# CAN.net
KiCad netlist of a schematic drawn in Altium Designer
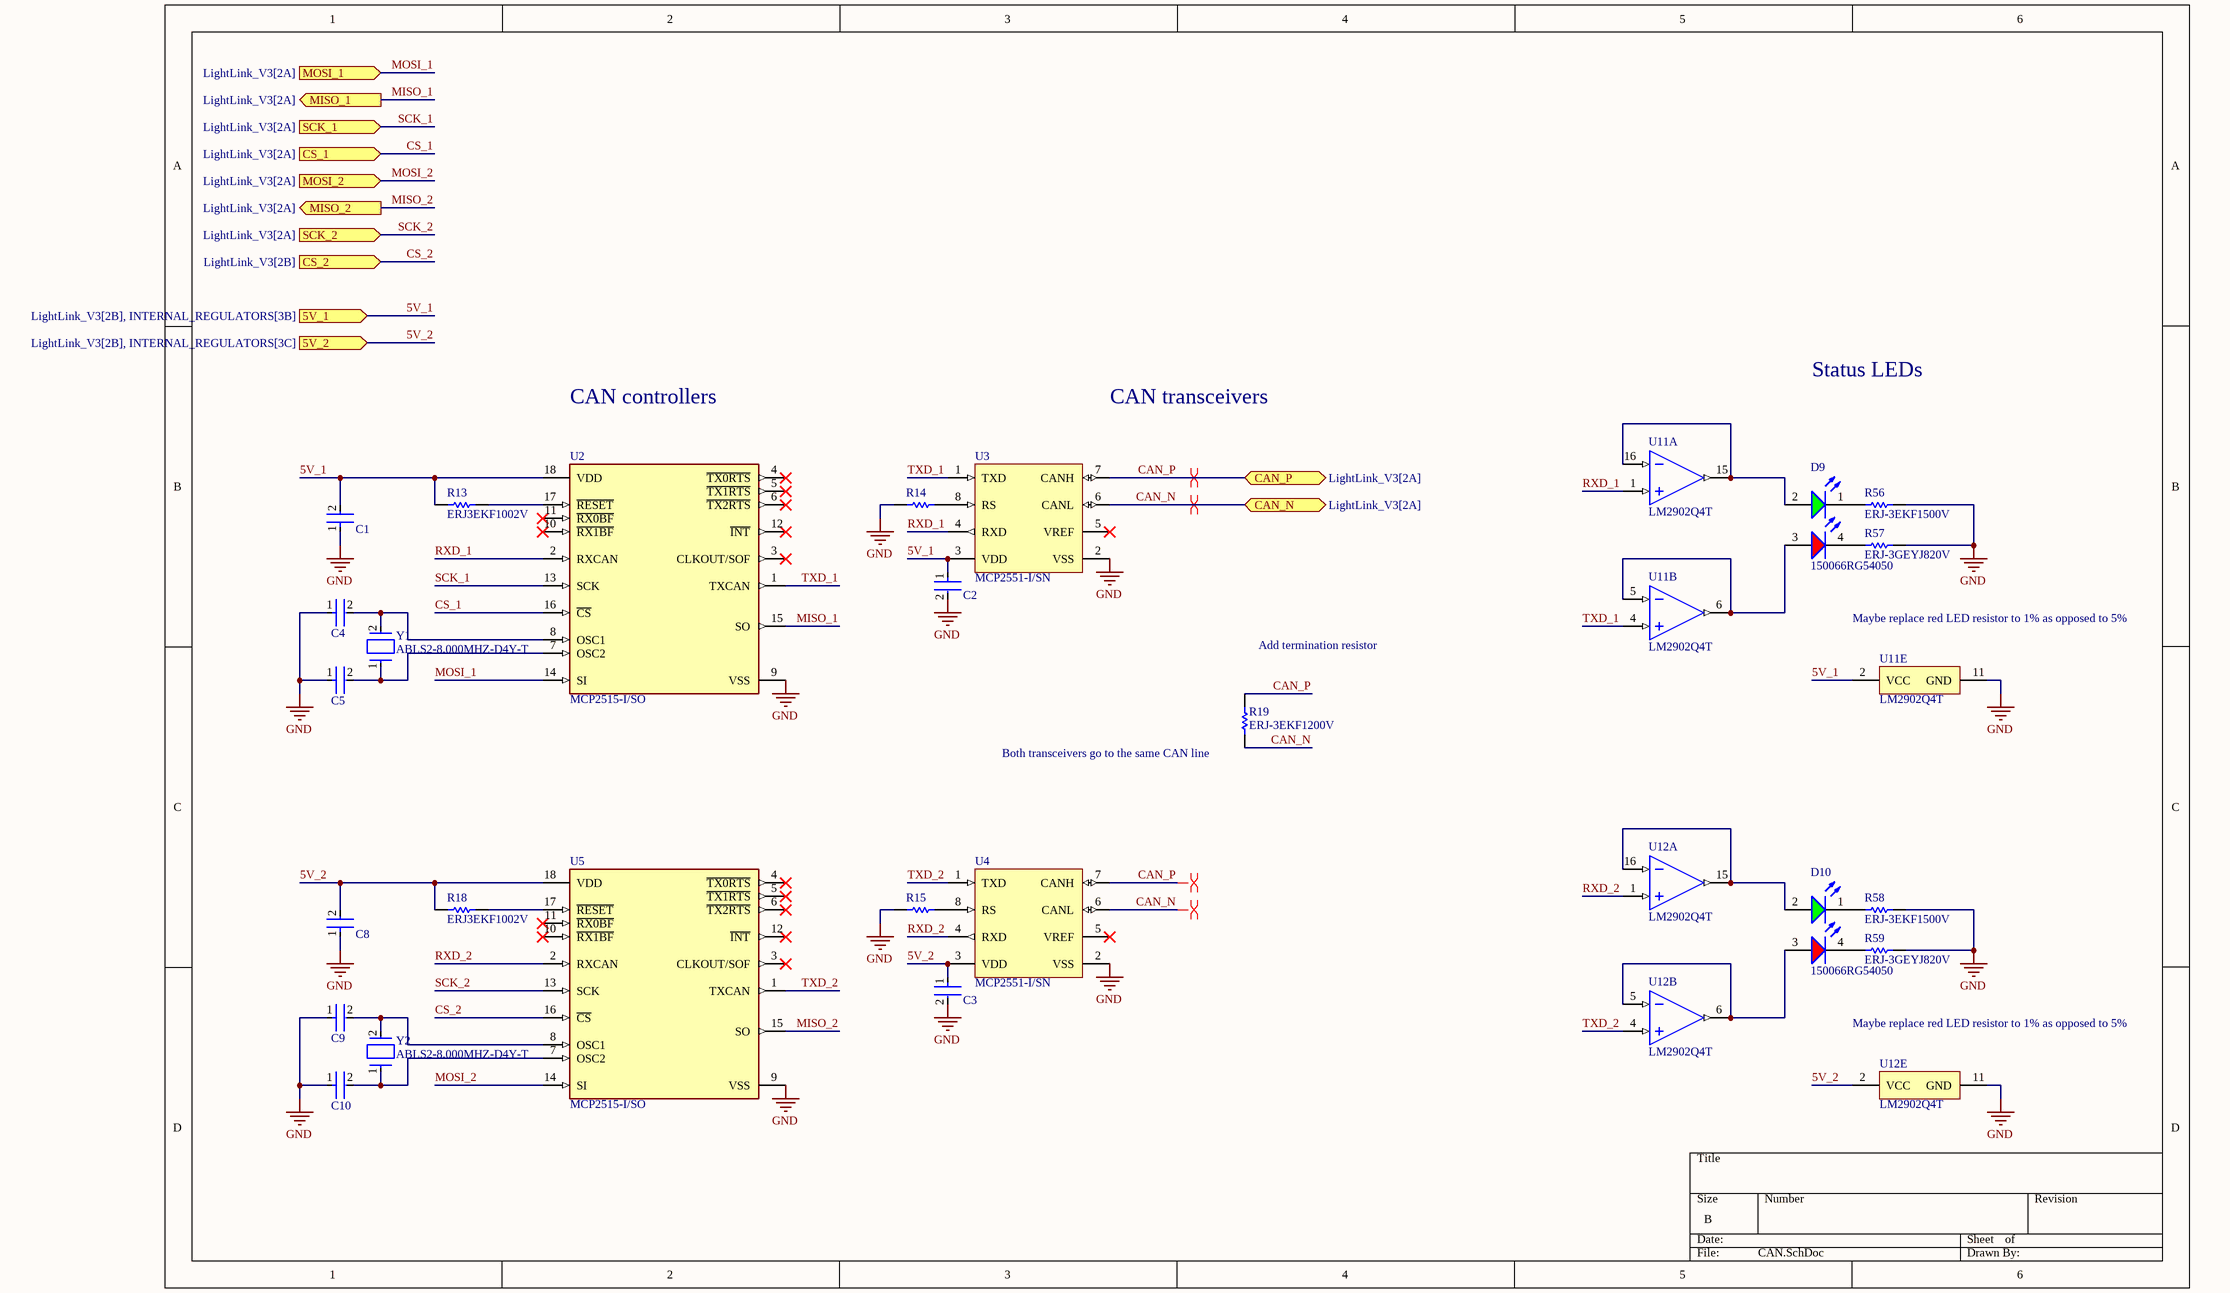
[diagram p0: CAN.SchDoc]

(export (version "E")
  (design (tool "Eeschema 10.0.6"))
  (components
    (comp (ref "C1")
      (value "GRM188R60J106ME47D")
      (footprint "FP-GRM188-0_1-e0_2_0_55-IPC_A")
      (description "Chip Multilayer Ceramic Capacitors for General Purpose, 0603, 10uF, X5R, 15%, 20%, 6.3V")
      (fields (field (name "VOLTAGE") "6.3V") (field (name "TOLERANCE") "20%"))
      (libsource (lib "Altium Content Vault") (part "02cd4be3c70576c341d710602a673aa"))
    )
    (comp (ref "C2")
      (value "C0402C104K8PACTU")
      (footprint "FP-C0402-BB-MFG")
      (description "CAP CER 0.1UF 10V X5R 0402")
      (fields (field (name "MANUFACTURER") "Kemet") (field (name "TOLERANCE") "0.1"))
      (libsource (lib "Altium Content Vault") (part "b4654b650e69147ec39a6b967a45e02"))
    )
    (comp (ref "C3")
      (value "C0402C104K8PACTU")
      (footprint "FP-C0402-BB-MFG")
      (description "CAP CER 0.1UF 10V X5R 0402")
      (fields (field (name "MANUFACTURER") "Kemet") (field (name "TOLERANCE") "0.1"))
      (libsource (lib "Altium Content Vault") (part "b4654b650e69147ec39a6b967a45e02"))
    )
    (comp (ref "C4")
      (value "GRM188R60J106ME47D")
      (footprint "FP-GRM188-0_1-e0_2_0_55-IPC_A")
      (description "Chip Multilayer Ceramic Capacitors for General Purpose, 0603, 10uF, X5R, 15%, 20%, 6.3V")
      (fields (field (name "VOLTAGE") "6.3V") (field (name "TOLERANCE") "20%"))
      (libsource (lib "Altium Content Vault") (part "02cd4be3c70576c341d710602a673aa"))
    )
    (comp (ref "C5")
      (value "GRM188R60J106ME47D")
      (footprint "FP-GRM188-0_1-e0_2_0_55-IPC_A")
      (description "Chip Multilayer Ceramic Capacitors for General Purpose, 0603, 10uF, X5R, 15%, 20%, 6.3V")
      (fields (field (name "VOLTAGE") "6.3V") (field (name "TOLERANCE") "20%"))
      (libsource (lib "Altium Content Vault") (part "02cd4be3c70576c341d710602a673aa"))
    )
    (comp (ref "C8")
      (value "GRM188R60J106ME47D")
      (footprint "FP-GRM188-0_1-e0_2_0_55-IPC_A")
      (description "Chip Multilayer Ceramic Capacitors for General Purpose, 0603, 10uF, X5R, 15%, 20%, 6.3V")
      (fields (field (name "VOLTAGE") "6.3V") (field (name "TOLERANCE") "20%"))
      (libsource (lib "Altium Content Vault") (part "02cd4be3c70576c341d710602a673aa"))
    )
    (comp (ref "C9")
      (value "GRM188R60J106ME47D")
      (footprint "FP-GRM188-0_1-e0_2_0_55-IPC_A")
      (description "Chip Multilayer Ceramic Capacitors for General Purpose, 0603, 10uF, X5R, 15%, 20%, 6.3V")
      (fields (field (name "VOLTAGE") "6.3V") (field (name "TOLERANCE") "20%"))
      (libsource (lib "Altium Content Vault") (part "02cd4be3c70576c341d710602a673aa"))
    )
    (comp (ref "C10")
      (value "GRM188R60J106ME47D")
      (footprint "FP-GRM188-0_1-e0_2_0_55-IPC_A")
      (description "Chip Multilayer Ceramic Capacitors for General Purpose, 0603, 10uF, X5R, 15%, 20%, 6.3V")
      (fields (field (name "VOLTAGE") "6.3V") (field (name "TOLERANCE") "20%"))
      (libsource (lib "Altium Content Vault") (part "02cd4be3c70576c341d710602a673aa"))
    )
    (comp (ref "D9")
      (value "150066RG54050")
      (footprint "WL-SBCD_0606")
      (description "Led, Red/Grn, 180Mcd/230Mcd, 624Nm/525Nm Rohs Compliant: Yes")
      (libsource (lib "uORocketry Hardware") (part "WL-SBCD_0606_Red & Green"))
    )
    (comp (ref "D10")
      (value "150066RG54050")
      (footprint "WL-SBCD_0606")
      (description "Led, Red/Grn, 180Mcd/230Mcd, 624Nm/525Nm Rohs Compliant: Yes")
      (libsource (lib "uORocketry Hardware") (part "WL-SBCD_0606_Red & Green"))
    )
    (comp (ref "R13")
      (value "ERJ3EKF1002V")
      (footprint "RESC1609X55X30LL15T15")
      (description "Chip Resistor, 10 KOhm, +/- 1%, 0.1 W, -55 to 155 degC, 0603 (1608 Metric), RoHS, Tape and Reel")
      (fields (field (name "TOLERANCE") "1%") (field (name "MANUFACTURER") "Panasonic"))
      (libsource (lib "Altium Content Vault") (part "RES-2"))
    )
    (comp (ref "R14")
      (value "ERJ3EKF1002V")
      (footprint "RESC1609X55X30LL15T15")
      (description "Chip Resistor, 10 KOhm, +/- 1%, 0.1 W, -55 to 155 degC, 0603 (1608 Metric), RoHS, Tape and Reel")
      (fields (field (name "TOLERANCE") "1%") (field (name "MANUFACTURER") "Panasonic"))
      (libsource (lib "Altium Content Vault") (part "RES-2"))
    )
    (comp (ref "R15")
      (value "ERJ3EKF1002V")
      (footprint "RESC1609X55X30LL15T15")
      (description "Chip Resistor, 10 KOhm, +/- 1%, 0.1 W, -55 to 155 degC, 0603 (1608 Metric), RoHS, Tape and Reel")
      (fields (field (name "TOLERANCE") "1%") (field (name "MANUFACTURER") "Panasonic"))
      (libsource (lib "Altium Content Vault") (part "RES-2"))
    )
    (comp (ref "R18")
      (value "ERJ3EKF1002V")
      (footprint "RESC1609X55X30LL15T15")
      (description "Chip Resistor, 10 KOhm, +/- 1%, 0.1 W, -55 to 155 degC, 0603 (1608 Metric), RoHS, Tape and Reel")
      (fields (field (name "TOLERANCE") "1%") (field (name "MANUFACTURER") "Panasonic"))
      (libsource (lib "Altium Content Vault") (part "RES-2"))
    )
    (comp (ref "R19")
      (value "ERJ-3EKF1200V")
      (footprint "RESC1609X55X30ML15T15")
      (description "Chip Resistor, 120 Ohm, +/- 1%, 0.1 W, -55 to 155 degC, 0603 (1608 Metric), RoHS, Tape and Reel")
      (fields (field (name "TOLERANCE") "1%") (field (name "MANUFACTURER") "Panasonic"))
      (libsource (lib "Altium Content Vault") (part "RES-2"))
    )
    (comp (ref "R56")
      (value "ERJ-3EKF1500V")
      (footprint "RESC1608X55X30NL15T15")
      (fields (field (name "MANUFACTURER") "Panasonic"))
      (libsource (lib "Altium Content Vault") (part "RES"))
    )
    (comp (ref "R57")
      (value "ERJ-3GEYJ820V")
      (footprint "RESC1608X55X30NL15T15")
      (fields (field (name "MANUFACTURER") "Panasonic"))
      (libsource (lib "Altium Content Vault") (part "RES"))
    )
    (comp (ref "R58")
      (value "ERJ-3EKF1500V")
      (footprint "RESC1608X55X30NL15T15")
      (fields (field (name "MANUFACTURER") "Panasonic"))
      (libsource (lib "Altium Content Vault") (part "RES"))
    )
    (comp (ref "R59")
      (value "ERJ-3GEYJ820V")
      (footprint "RESC1608X55X30NL15T15")
      (fields (field (name "MANUFACTURER") "Panasonic"))
      (libsource (lib "Altium Content Vault") (part "RES"))
    )
    (comp (ref "U2")
      (value "MCP2515-I/SO")
      (footprint "FP-C04-051-MFG")
      (description "IC CAN CONTROLLER W/SPI 18SOIC")
      (fields
        (field (name "MANUFACTURER") "Microchip")
        (field (name "OCTOPART") "https://octopart.com/mcp2515-i%2Fso-microchip-430187")
      )
      (libsource (lib "Altium Content Vault") (part "1c78ea6ff576bac94664e2637e1b479"))
    )
    (comp (ref "U3")
      (value "MCP2551-I/SN")
      (footprint "MCHP-SN8_V")
      (fields (field (name "MANUFACTURER") "Microchip"))
      (libsource (lib "Altium Content Vault") (part "MCHP-MCP2551-SN8"))
    )
    (comp (ref "U4")
      (value "MCP2551-I/SN")
      (footprint "MCHP-SN8_V")
      (fields (field (name "MANUFACTURER") "Microchip"))
      (libsource (lib "Altium Content Vault") (part "MCHP-MCP2551-SN8"))
    )
    (comp (ref "U5")
      (value "MCP2515-I/SO")
      (footprint "FP-C04-051-MFG")
      (description "IC CAN CONTROLLER W/SPI 18SOIC")
      (fields
        (field (name "MANUFACTURER") "Microchip")
        (field (name "OCTOPART") "https://octopart.com/mcp2515-i%2Fso-microchip-430187")
      )
      (libsource (lib "Altium Content Vault") (part "1c78ea6ff576bac94664e2637e1b479"))
    )
    (comp (ref "U11")
      (value "LM2902Q4T")
      (footprint "LM2902Q4T-Footprint-1")
      (description "LM2902 Series 30 V 1.3 MHz Low-Power Quad Operational Amplifier - QFN-16 (3x3)")
      (libsource (lib "uORocketry Hardware") (part "LM2902Q4T"))
    )
    (comp (ref "U12")
      (value "LM2902Q4T")
      (footprint "LM2902Q4T-Footprint-1")
      (description "LM2902 Series 30 V 1.3 MHz Low-Power Quad Operational Amplifier - QFN-16 (3x3)")
      (libsource (lib "uORocketry Hardware") (part "LM2902Q4T"))
    )
    (comp (ref "Y1")
      (value "ABLS2-8.000MHZ-D4Y-T")
      (footprint "FP-ABLS2-MFG")
      (description "CRYSTAL 8.0000MHZ 18PF SMD")
      (fields (field (name "TOLERANCE") "30ppm"))
      (libsource (lib "Altium Content Vault") (part "c23a69dc6c9e2f18f2079038eb95dd1"))
    )
    (comp (ref "Y2")
      (value "ABLS2-8.000MHZ-D4Y-T")
      (footprint "FP-ABLS2-MFG")
      (description "CRYSTAL 8.0000MHZ 18PF SMD")
      (fields (field (name "TOLERANCE") "30ppm"))
      (libsource (lib "Altium Content Vault") (part "c23a69dc6c9e2f18f2079038eb95dd1"))
    )
  )
  (nets
    (net (code "1") (name "/5V_1") (class "Default")
      (node (ref "C1") (pin "2") (pinfunction "2_2") (pintype "passive"))
      (node (ref "C2") (pin "1") (pinfunction "1_1") (pintype "passive"))
      (node (ref "R13") (pin "1") (pinfunction "1_1") (pintype "passive"))
      (node (ref "U11") (pin "2") (pinfunction "VCC_2") (pintype "power_in"))
      (node (ref "U2") (pin "18") (pinfunction "VDD_18") (pintype "power_in"))
      (node (ref "U3") (pin "3") (pinfunction "VDD_3") (pintype "power_in"))
    )
    (net (code "2") (name "/5V_2") (class "Default")
      (node (ref "C3") (pin "1") (pinfunction "1_1") (pintype "passive"))
      (node (ref "C8") (pin "2") (pinfunction "2_2") (pintype "passive"))
      (node (ref "R18") (pin "1") (pinfunction "1_1") (pintype "passive"))
      (node (ref "U12") (pin "2") (pinfunction "VCC_2") (pintype "power_in"))
      (node (ref "U4") (pin "3") (pinfunction "VDD_3") (pintype "power_in"))
      (node (ref "U5") (pin "18") (pinfunction "VDD_18") (pintype "power_in"))
    )
    (net (code "3") (name "/CAN_N") (class "Default")
      (node (ref "R19") (pin "1") (pinfunction "1_1") (pintype "passive"))
      (node (ref "U3") (pin "6") (pinfunction "CANL_6") (pintype "bidirectional"))
      (node (ref "U4") (pin "6") (pinfunction "CANL_6") (pintype "bidirectional"))
    )
    (net (code "4") (name "/CAN_P") (class "Default")
      (node (ref "R19") (pin "2") (pinfunction "2_2") (pintype "passive"))
      (node (ref "U3") (pin "7") (pinfunction "CANH_7") (pintype "bidirectional"))
      (node (ref "U4") (pin "7") (pinfunction "CANH_7") (pintype "bidirectional"))
    )
    (net (code "5") (name "/CS_1") (class "Default")
      (node (ref "U2") (pin "16") (pinfunction "~{CS}_16") (pintype "input"))
    )
    (net (code "6") (name "/CS_2") (class "Default")
      (node (ref "U5") (pin "16") (pinfunction "~{CS}_16") (pintype "input"))
    )
    (net (code "7") (name "/MISO_1") (class "Default")
      (node (ref "U2") (pin "15") (pinfunction "SO_15") (pintype "output"))
    )
    (net (code "8") (name "/MISO_2") (class "Default")
      (node (ref "U5") (pin "15") (pinfunction "SO_15") (pintype "output"))
    )
    (net (code "9") (name "/MOSI_1") (class "Default")
      (node (ref "U2") (pin "14") (pinfunction "SI_14") (pintype "input"))
    )
    (net (code "10") (name "/MOSI_2") (class "Default")
      (node (ref "U5") (pin "14") (pinfunction "SI_14") (pintype "input"))
    )
    (net (code "11") (name "/RXD_1") (class "Default")
      (node (ref "U11") (pin "1") (pinfunction "1IN+_1") (pintype "input"))
      (node (ref "U2") (pin "2") (pinfunction "RXCAN_2") (pintype "input"))
      (node (ref "U3") (pin "4") (pinfunction "RXD_4") (pintype "output"))
    )
    (net (code "12") (name "/RXD_2") (class "Default")
      (node (ref "U12") (pin "1") (pinfunction "1IN+_1") (pintype "input"))
      (node (ref "U4") (pin "4") (pinfunction "RXD_4") (pintype "output"))
      (node (ref "U5") (pin "2") (pinfunction "RXCAN_2") (pintype "input"))
    )
    (net (code "13") (name "/SCK_1") (class "Default")
      (node (ref "U2") (pin "13") (pinfunction "SCK_13") (pintype "input"))
    )
    (net (code "14") (name "/SCK_2") (class "Default")
      (node (ref "U5") (pin "13") (pinfunction "SCK_13") (pintype "input"))
    )
    (net (code "15") (name "/TXD_1") (class "Default")
      (node (ref "U11") (pin "4") (pinfunction "2IN+_4") (pintype "input"))
      (node (ref "U2") (pin "1") (pinfunction "TXCAN_1") (pintype "output"))
      (node (ref "U3") (pin "1") (pinfunction "TXD_1") (pintype "input"))
    )
    (net (code "16") (name "/TXD_2") (class "Default")
      (node (ref "U12") (pin "4") (pinfunction "2IN+_4") (pintype "input"))
      (node (ref "U4") (pin "1") (pinfunction "TXD_1") (pintype "input"))
      (node (ref "U5") (pin "1") (pinfunction "TXCAN_1") (pintype "output"))
    )
    (net (code "17") (name "GND") (class "Default")
      (node (ref "C1") (pin "1") (pinfunction "1_1") (pintype "passive"))
      (node (ref "C10") (pin "1") (pinfunction "1_1") (pintype "passive"))
      (node (ref "C2") (pin "2") (pinfunction "2_2") (pintype "passive"))
      (node (ref "C3") (pin "2") (pinfunction "2_2") (pintype "passive"))
      (node (ref "C4") (pin "1") (pinfunction "1_1") (pintype "passive"))
      (node (ref "C5") (pin "1") (pinfunction "1_1") (pintype "passive"))
      (node (ref "C8") (pin "1") (pinfunction "1_1") (pintype "passive"))
      (node (ref "C9") (pin "1") (pinfunction "1_1") (pintype "passive"))
      (node (ref "R14") (pin "1") (pinfunction "1_1") (pintype "passive"))
      (node (ref "R15") (pin "1") (pinfunction "1_1") (pintype "passive"))
      (node (ref "R56") (pin "2") (pinfunction "2_2") (pintype "passive"))
      (node (ref "R57") (pin "2") (pinfunction "2_2") (pintype "passive"))
      (node (ref "R58") (pin "2") (pinfunction "2_2") (pintype "passive"))
      (node (ref "R59") (pin "2") (pinfunction "2_2") (pintype "passive"))
      (node (ref "U11") (pin "11") (pinfunction "GND_11") (pintype "power_in"))
      (node (ref "U12") (pin "11") (pinfunction "GND_11") (pintype "power_in"))
      (node (ref "U2") (pin "9") (pinfunction "VSS_9") (pintype "power_in"))
      (node (ref "U3") (pin "2") (pinfunction "VSS_2") (pintype "power_in"))
      (node (ref "U4") (pin "2") (pinfunction "VSS_2") (pintype "power_in"))
      (node (ref "U5") (pin "9") (pinfunction "VSS_9") (pintype "power_in"))
    )
    (net (code "18") (name "Net-(D9-K-Pad1)") (class "Default")
      (node (ref "D9") (pin "1") (pinfunction "K_1") (pintype "passive"))
      (node (ref "R56") (pin "1") (pinfunction "1_1") (pintype "passive"))
    )
    (net (code "19") (name "Net-(D9-K-Pad4)") (class "Default")
      (node (ref "D9") (pin "4") (pinfunction "K_4") (pintype "passive"))
      (node (ref "R57") (pin "1") (pinfunction "1_1") (pintype "passive"))
    )
    (net (code "20") (name "Net-(D10-K-Pad1)") (class "Default")
      (node (ref "D10") (pin "1") (pinfunction "K_1") (pintype "passive"))
      (node (ref "R58") (pin "1") (pinfunction "1_1") (pintype "passive"))
    )
    (net (code "21") (name "Net-(D10-K-Pad4)") (class "Default")
      (node (ref "D10") (pin "4") (pinfunction "K_4") (pintype "passive"))
      (node (ref "R59") (pin "1") (pinfunction "1_1") (pintype "passive"))
    )
    (net (code "22") (name "Net-(U2-OSC1)") (class "Default")
      (node (ref "C4") (pin "2") (pinfunction "2_2") (pintype "passive"))
      (node (ref "U2") (pin "8") (pinfunction "OSC1_8") (pintype "input"))
      (node (ref "Y1") (pin "2") (pinfunction "2_2") (pintype "passive"))
    )
    (net (code "23") (name "Net-(U2-OSC2)") (class "Default")
      (node (ref "C5") (pin "2") (pinfunction "2_2") (pintype "passive"))
      (node (ref "U2") (pin "7") (pinfunction "OSC2_7") (pintype "input"))
      (node (ref "Y1") (pin "1") (pinfunction "1_1") (pintype "passive"))
    )
    (net (code "24") (name "Net-(U2-~{RESET})") (class "Default")
      (node (ref "R13") (pin "2") (pinfunction "2_2") (pintype "passive"))
      (node (ref "U2") (pin "17") (pinfunction "~{RESET}_17") (pintype "input"))
    )
    (net (code "25") (name "Net-(U3-RS)") (class "Default")
      (node (ref "R14") (pin "2") (pinfunction "2_2") (pintype "passive"))
      (node (ref "U3") (pin "8") (pinfunction "RS_8") (pintype "input"))
    )
    (net (code "26") (name "Net-(U4-RS)") (class "Default")
      (node (ref "R15") (pin "2") (pinfunction "2_2") (pintype "passive"))
      (node (ref "U4") (pin "8") (pinfunction "RS_8") (pintype "input"))
    )
    (net (code "27") (name "Net-(U5-OSC1)") (class "Default")
      (node (ref "C9") (pin "2") (pinfunction "2_2") (pintype "passive"))
      (node (ref "U5") (pin "8") (pinfunction "OSC1_8") (pintype "input"))
      (node (ref "Y2") (pin "2") (pinfunction "2_2") (pintype "passive"))
    )
    (net (code "28") (name "Net-(U5-OSC2)") (class "Default")
      (node (ref "C10") (pin "2") (pinfunction "2_2") (pintype "passive"))
      (node (ref "U5") (pin "7") (pinfunction "OSC2_7") (pintype "input"))
      (node (ref "Y2") (pin "1") (pinfunction "1_1") (pintype "passive"))
    )
    (net (code "29") (name "Net-(U5-~{RESET})") (class "Default")
      (node (ref "R18") (pin "2") (pinfunction "2_2") (pintype "passive"))
      (node (ref "U5") (pin "17") (pinfunction "~{RESET}_17") (pintype "input"))
    )
    (net (code "30") (name "Net-(U11A-1IN-)") (class "Default")
      (node (ref "D9") (pin "2") (pinfunction "A_2") (pintype "passive"))
      (node (ref "U11") (pin "15") (pinfunction "1OUT_15") (pintype "output"))
      (node (ref "U11") (pin "16") (pinfunction "1IN-_16") (pintype "input"))
    )
    (net (code "31") (name "Net-(U11B-2IN-)") (class "Default")
      (node (ref "D9") (pin "3") (pinfunction "A_3") (pintype "passive"))
      (node (ref "U11") (pin "5") (pinfunction "2IN-_5") (pintype "input"))
      (node (ref "U11") (pin "6") (pinfunction "2OUT_6") (pintype "output"))
    )
    (net (code "32") (name "Net-(U12A-1IN-)") (class "Default")
      (node (ref "D10") (pin "2") (pinfunction "A_2") (pintype "passive"))
      (node (ref "U12") (pin "15") (pinfunction "1OUT_15") (pintype "output"))
      (node (ref "U12") (pin "16") (pinfunction "1IN-_16") (pintype "input"))
    )
    (net (code "33") (name "Net-(U12B-2IN-)") (class "Default")
      (node (ref "D10") (pin "3") (pinfunction "A_3") (pintype "passive"))
      (node (ref "U12") (pin "5") (pinfunction "2IN-_5") (pintype "input"))
      (node (ref "U12") (pin "6") (pinfunction "2OUT_6") (pintype "output"))
    )
    (net (code "34") (name "unconnected-(U2-CLKOUT{slash}SOF-Pad3)") (class "Default")
      (node (ref "U2") (pin "3") (pinfunction "CLKOUT/SOF_3") (pintype "output+no_connect"))
    )
    (net (code "35") (name "unconnected-(U2-~{INT}-Pad12)") (class "Default")
      (node (ref "U2") (pin "12") (pinfunction "~{INT}_12") (pintype "output+no_connect"))
    )
    (net (code "36") (name "unconnected-(U2-~{RX0BF}-Pad11)") (class "Default")
      (node (ref "U2") (pin "11") (pinfunction "~{RX0BF}_11") (pintype "input+no_connect"))
    )
    (net (code "37") (name "unconnected-(U2-~{RX1BF}-Pad10)") (class "Default")
      (node (ref "U2") (pin "10") (pinfunction "~{RX1BF}_10") (pintype "input+no_connect"))
    )
    (net (code "38") (name "unconnected-(U2-~{TX0RTS}-Pad4)") (class "Default")
      (node (ref "U2") (pin "4") (pinfunction "~{TX0RTS}_4") (pintype "output+no_connect"))
    )
    (net (code "39") (name "unconnected-(U2-~{TX1RTS}-Pad5)") (class "Default")
      (node (ref "U2") (pin "5") (pinfunction "~{TX1RTS}_5") (pintype "output+no_connect"))
    )
    (net (code "40") (name "unconnected-(U2-~{TX2RTS}-Pad6)") (class "Default")
      (node (ref "U2") (pin "6") (pinfunction "~{TX2RTS}_6") (pintype "output+no_connect"))
    )
    (net (code "41") (name "unconnected-(U3-VREF-Pad5)") (class "Default")
      (node (ref "U3") (pin "5") (pinfunction "VREF_5") (pintype "power_in+no_connect"))
    )
    (net (code "42") (name "unconnected-(U4-VREF-Pad5)") (class "Default")
      (node (ref "U4") (pin "5") (pinfunction "VREF_5") (pintype "power_in+no_connect"))
    )
    (net (code "43") (name "unconnected-(U5-CLKOUT{slash}SOF-Pad3)") (class "Default")
      (node (ref "U5") (pin "3") (pinfunction "CLKOUT/SOF_3") (pintype "output+no_connect"))
    )
    (net (code "44") (name "unconnected-(U5-~{INT}-Pad12)") (class "Default")
      (node (ref "U5") (pin "12") (pinfunction "~{INT}_12") (pintype "output+no_connect"))
    )
    (net (code "45") (name "unconnected-(U5-~{RX0BF}-Pad11)") (class "Default")
      (node (ref "U5") (pin "11") (pinfunction "~{RX0BF}_11") (pintype "input+no_connect"))
    )
    (net (code "46") (name "unconnected-(U5-~{RX1BF}-Pad10)") (class "Default")
      (node (ref "U5") (pin "10") (pinfunction "~{RX1BF}_10") (pintype "input+no_connect"))
    )
    (net (code "47") (name "unconnected-(U5-~{TX0RTS}-Pad4)") (class "Default")
      (node (ref "U5") (pin "4") (pinfunction "~{TX0RTS}_4") (pintype "output+no_connect"))
    )
    (net (code "48") (name "unconnected-(U5-~{TX1RTS}-Pad5)") (class "Default")
      (node (ref "U5") (pin "5") (pinfunction "~{TX1RTS}_5") (pintype "output+no_connect"))
    )
    (net (code "49") (name "unconnected-(U5-~{TX2RTS}-Pad6)") (class "Default")
      (node (ref "U5") (pin "6") (pinfunction "~{TX2RTS}_6") (pintype "output+no_connect"))
    )
  )
)
